# USB_to_UART_Controler.net
KiCad netlist of a schematic drawn in EAGLE
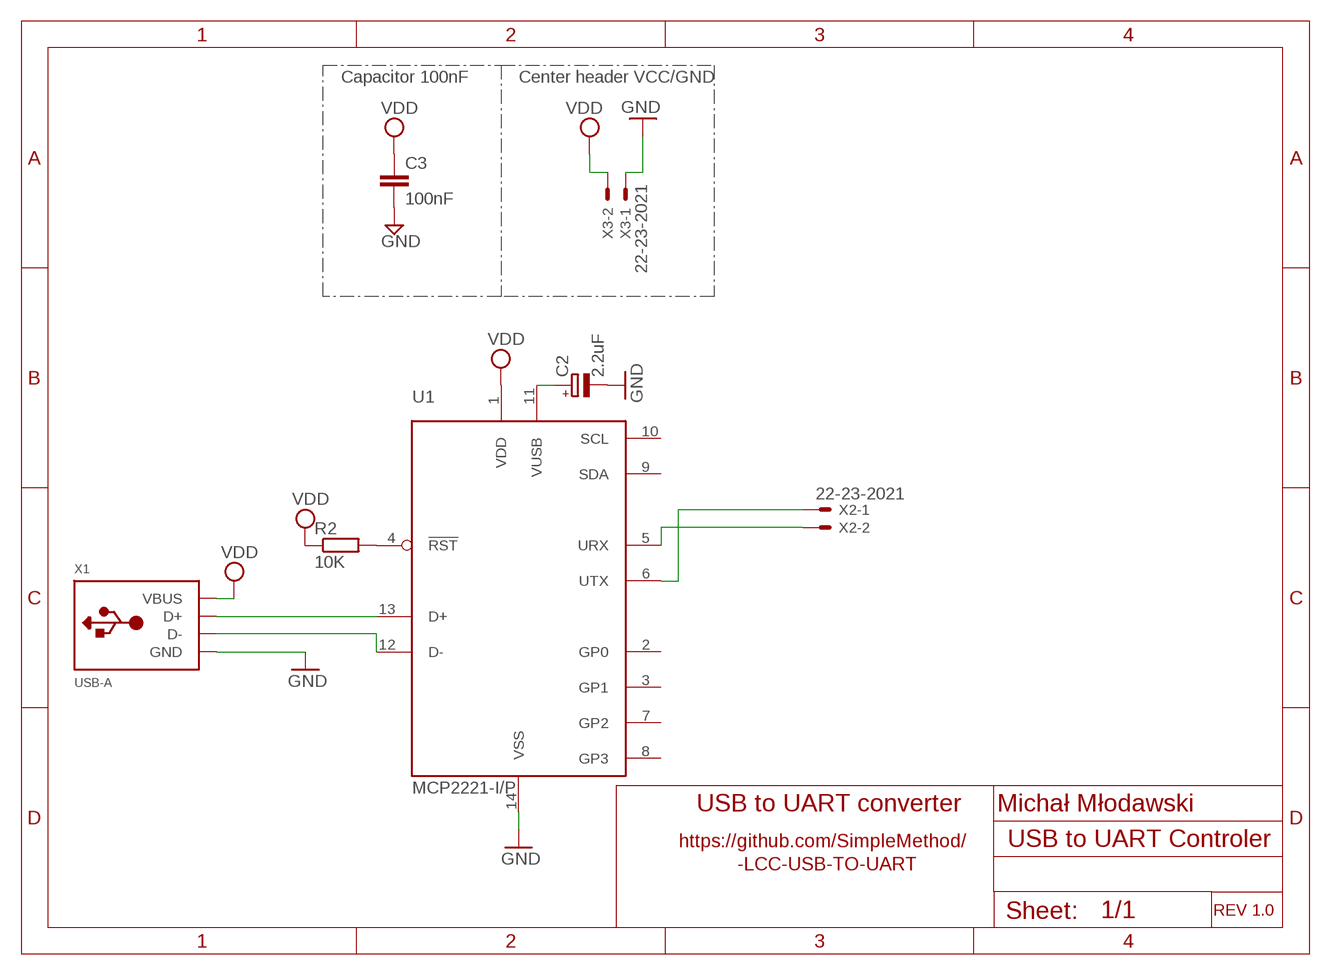
[diagram p0: schematic, sheet 1]

(export (version "E")
  (design (tool "Eeschema 10.0.6"))
  (components
    (comp (ref "C2")
      (value "2.2uF")
      (footprint "eagle-import:TAP5-45")
      (libsource (lib "eagle-import") (part "CPOL-EUTAP5-45"))
    )
    (comp (ref "C3")
      (value "100nF")
      (footprint "eagle-import:C2.5-3")
      (libsource (lib "eagle-import") (part "C2,5-3"))
    )
    (comp (ref "R2")
      (value "10K")
      (footprint "eagle-import:0204V")
      (libsource (lib "eagle-import") (part "R-EU_0204/2V"))
    )
    (comp (ref "U1")
      (value "MCP2221-I/P")
      (footprint "eagle-import:DIL14")
      (libsource (lib "eagle-import") (part "MCP2221-I/P"))
    )
    (comp (ref "X1")
      (value "USB-A")
      (footprint "eagle-import:MOLEX_480371000")
      (libsource (lib "eagle-import") (part "USB-A"))
    )
    (comp (ref "X2")
      (value "22-23-2021")
      (footprint "eagle-import:22-23-2021")
      (fields (field (name "MF") "MOLEX"))
      (libsource (lib "eagle-import") (part "22-23-2021"))
    )
    (comp (ref "X3")
      (value "22-23-2021")
      (footprint "eagle-import:22-23-2021")
      (fields (field (name "MF") "MOLEX"))
      (libsource (lib "eagle-import") (part "22-23-2021"))
    )
  )
  (nets
    (net (code "1") (name "GND") (class "Default")
      (node (ref "C2") (pin "-") (pinfunction "-_-") (pintype "passive"))
      (node (ref "C3") (pin "2") (pinfunction "2_2") (pintype "passive"))
      (node (ref "U1") (pin "14") (pinfunction "VSS_14") (pintype "power_in"))
      (node (ref "X1") (pin "4") (pinfunction "GND_4") (pintype "power_in"))
      (node (ref "X3") (pin "1") (pinfunction "S_1") (pintype "passive"))
    )
    (net (code "2") (name "Net-(U1-D+)") (class "Default")
      (node (ref "U1") (pin "13") (pinfunction "D+_13") (pintype "bidirectional"))
      (node (ref "X1") (pin "3") (pinfunction "D+_3") (pintype "bidirectional"))
    )
    (net (code "3") (name "Net-(U1-D-)") (class "Default")
      (node (ref "U1") (pin "12") (pinfunction "D-_12") (pintype "bidirectional"))
      (node (ref "X1") (pin "2") (pinfunction "D-_2") (pintype "bidirectional"))
    )
    (net (code "4") (name "Net-(U1-URX)") (class "Default")
      (node (ref "U1") (pin "5") (pinfunction "URX_5") (pintype "input"))
      (node (ref "X2") (pin "2") (pinfunction "S_2") (pintype "passive"))
    )
    (net (code "5") (name "Net-(U1-UTX)") (class "Default")
      (node (ref "U1") (pin "6") (pinfunction "UTX_6") (pintype "output"))
      (node (ref "X2") (pin "1") (pinfunction "S_1") (pintype "passive"))
    )
    (net (code "6") (name "Net-(U1-VUSB)") (class "Default")
      (node (ref "C2") (pin "+") (pinfunction "+_+") (pintype "passive"))
      (node (ref "U1") (pin "11") (pinfunction "VUSB_11") (pintype "power_in"))
    )
    (net (code "7") (name "Net-(U1-~{RST})") (class "Default")
      (node (ref "R2") (pin "2") (pinfunction "2_2") (pintype "passive"))
      (node (ref "U1") (pin "4") (pinfunction "~{RST}_4") (pintype "input"))
    )
    (net (code "8") (name "VDD") (class "Default")
      (node (ref "C3") (pin "1") (pinfunction "1_1") (pintype "passive"))
      (node (ref "R2") (pin "1") (pinfunction "1_1") (pintype "passive"))
      (node (ref "U1") (pin "1") (pinfunction "VDD_1") (pintype "power_in"))
      (node (ref "X1") (pin "1") (pinfunction "VBUS_1") (pintype "power_in"))
      (node (ref "X3") (pin "2") (pinfunction "S_2") (pintype "passive"))
    )
    (net (code "9") (name "unconnected-(U1-GP0-Pad2)") (class "Default")
      (node (ref "U1") (pin "2") (pinfunction "GP0_2") (pintype "bidirectional"))
    )
    (net (code "10") (name "unconnected-(U1-GP1-Pad3)") (class "Default")
      (node (ref "U1") (pin "3") (pinfunction "GP1_3") (pintype "bidirectional"))
    )
    (net (code "11") (name "unconnected-(U1-GP2-Pad7)") (class "Default")
      (node (ref "U1") (pin "7") (pinfunction "GP2_7") (pintype "bidirectional"))
    )
    (net (code "12") (name "unconnected-(U1-GP3-Pad8)") (class "Default")
      (node (ref "U1") (pin "8") (pinfunction "GP3_8") (pintype "bidirectional"))
    )
    (net (code "13") (name "unconnected-(U1-SCL-Pad10)") (class "Default")
      (node (ref "U1") (pin "10") (pinfunction "SCL_10") (pintype "output"))
    )
    (net (code "14") (name "unconnected-(U1-SDA-Pad9)") (class "Default")
      (node (ref "U1") (pin "9") (pinfunction "SDA_9") (pintype "bidirectional"))
    )
  )
)
